# MPL115A1.net
KiCad netlist of a schematic drawn in EAGLE
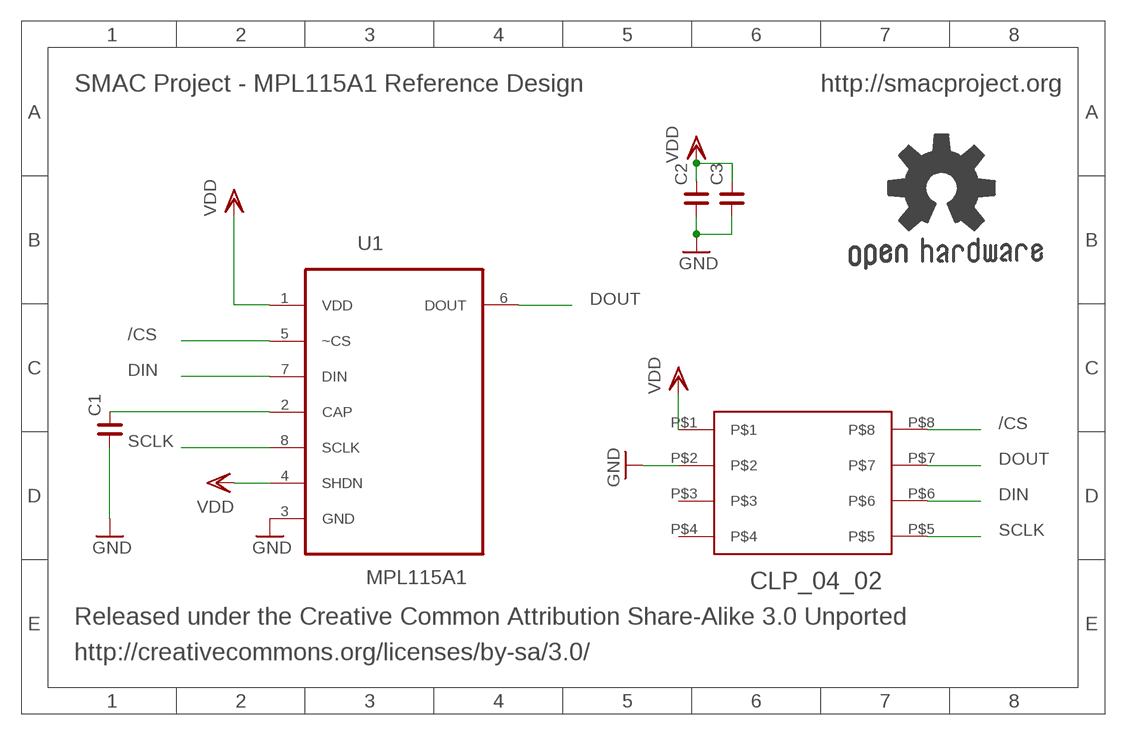
[diagram p0: schematic, sheet 1]

(export (version "E")
  (design (tool "Eeschema 10.0.6"))
  (components
    (comp (ref "C1")
      (value "C_0402")
      (footprint "eagle-import:C0402")
      (libsource (lib "eagle-import") (part "C_0402"))
    )
    (comp (ref "C2")
      (value "C_0402")
      (footprint "eagle-import:C0402")
      (libsource (lib "eagle-import") (part "C_0402"))
    )
    (comp (ref "C3")
      (value "C_0402")
      (footprint "eagle-import:C0402")
      (libsource (lib "eagle-import") (part "C_0402"))
    )
    (comp (ref "GOLD_ORB_SM2")
      (value "OSHWLOGO_REF_SM")
      (footprint "eagle-import:OSHW2REF")
      (libsource (lib "eagle-import") (part "OSHWLOGO_REF_SM"))
    )
    (comp (ref "U$1")
      (value "CLP_04_02")
      (footprint "eagle-import:CLP-104")
      (libsource (lib "eagle-import") (part "CLP_04_02"))
    )
    (comp (ref "U1")
      (value "MPL115A1")
      (footprint "eagle-import:LGA8R125P0X4_500X300X120")
      (libsource (lib "eagle-import") (part "MPL115A1"))
    )
  )
  (nets
    (net (code "1") (name "/DIN") (class "Default")
      (node (ref "U$1") (pin "P$6") (pinfunction "P$6_P$6") (pintype "bidirectional"))
      (node (ref "U1") (pin "7") (pinfunction "DIN_7") (pintype "input"))
    )
    (net (code "2") (name "/DOUT") (class "Default")
      (node (ref "U$1") (pin "P$7") (pinfunction "P$7_P$7") (pintype "bidirectional"))
      (node (ref "U1") (pin "6") (pinfunction "DOUT_6") (pintype "output"))
    )
    (net (code "3") (name "/SCLK") (class "Default")
      (node (ref "U$1") (pin "P$5") (pinfunction "P$5_P$5") (pintype "bidirectional"))
      (node (ref "U1") (pin "8") (pinfunction "SCLK_8") (pintype "input"))
    )
    (net (code "4") (name "/{slash}CS") (class "Default")
      (node (ref "U$1") (pin "P$8") (pinfunction "P$8_P$8") (pintype "bidirectional"))
      (node (ref "U1") (pin "5") (pinfunction "~{CS}_5") (pintype "input"))
    )
    (net (code "5") (name "GND") (class "Default")
      (node (ref "C1") (pin "1") (pinfunction "1_1") (pintype "passive"))
      (node (ref "C2") (pin "1") (pinfunction "1_1") (pintype "passive"))
      (node (ref "C3") (pin "1") (pinfunction "1_1") (pintype "passive"))
      (node (ref "U$1") (pin "P$2") (pinfunction "P$2_P$2") (pintype "bidirectional"))
      (node (ref "U1") (pin "3") (pinfunction "GND_3") (pintype "passive"))
    )
    (net (code "6") (name "Net-(U1-CAP)") (class "Default")
      (node (ref "C1") (pin "2") (pinfunction "2_2") (pintype "passive"))
      (node (ref "U1") (pin "2") (pinfunction "CAP_2") (pintype "input"))
    )
    (net (code "7") (name "VDD") (class "Default")
      (node (ref "C2") (pin "2") (pinfunction "2_2") (pintype "passive"))
      (node (ref "C3") (pin "2") (pinfunction "2_2") (pintype "passive"))
      (node (ref "U$1") (pin "P$1") (pinfunction "P$1_P$1") (pintype "bidirectional"))
      (node (ref "U1") (pin "1") (pinfunction "VDD_1") (pintype "power_in"))
      (node (ref "U1") (pin "4") (pinfunction "SHDN_4") (pintype "input"))
    )
    (net (code "8") (name "unconnected-(U$1-PadP$3)") (class "Default")
      (node (ref "U$1") (pin "P$3") (pinfunction "P$3_P$3") (pintype "bidirectional"))
    )
    (net (code "9") (name "unconnected-(U$1-PadP$4)") (class "Default")
      (node (ref "U$1") (pin "P$4") (pinfunction "P$4_P$4") (pintype "bidirectional"))
    )
  )
)
